# power.net
KiCad netlist of a schematic drawn in Altium Designer
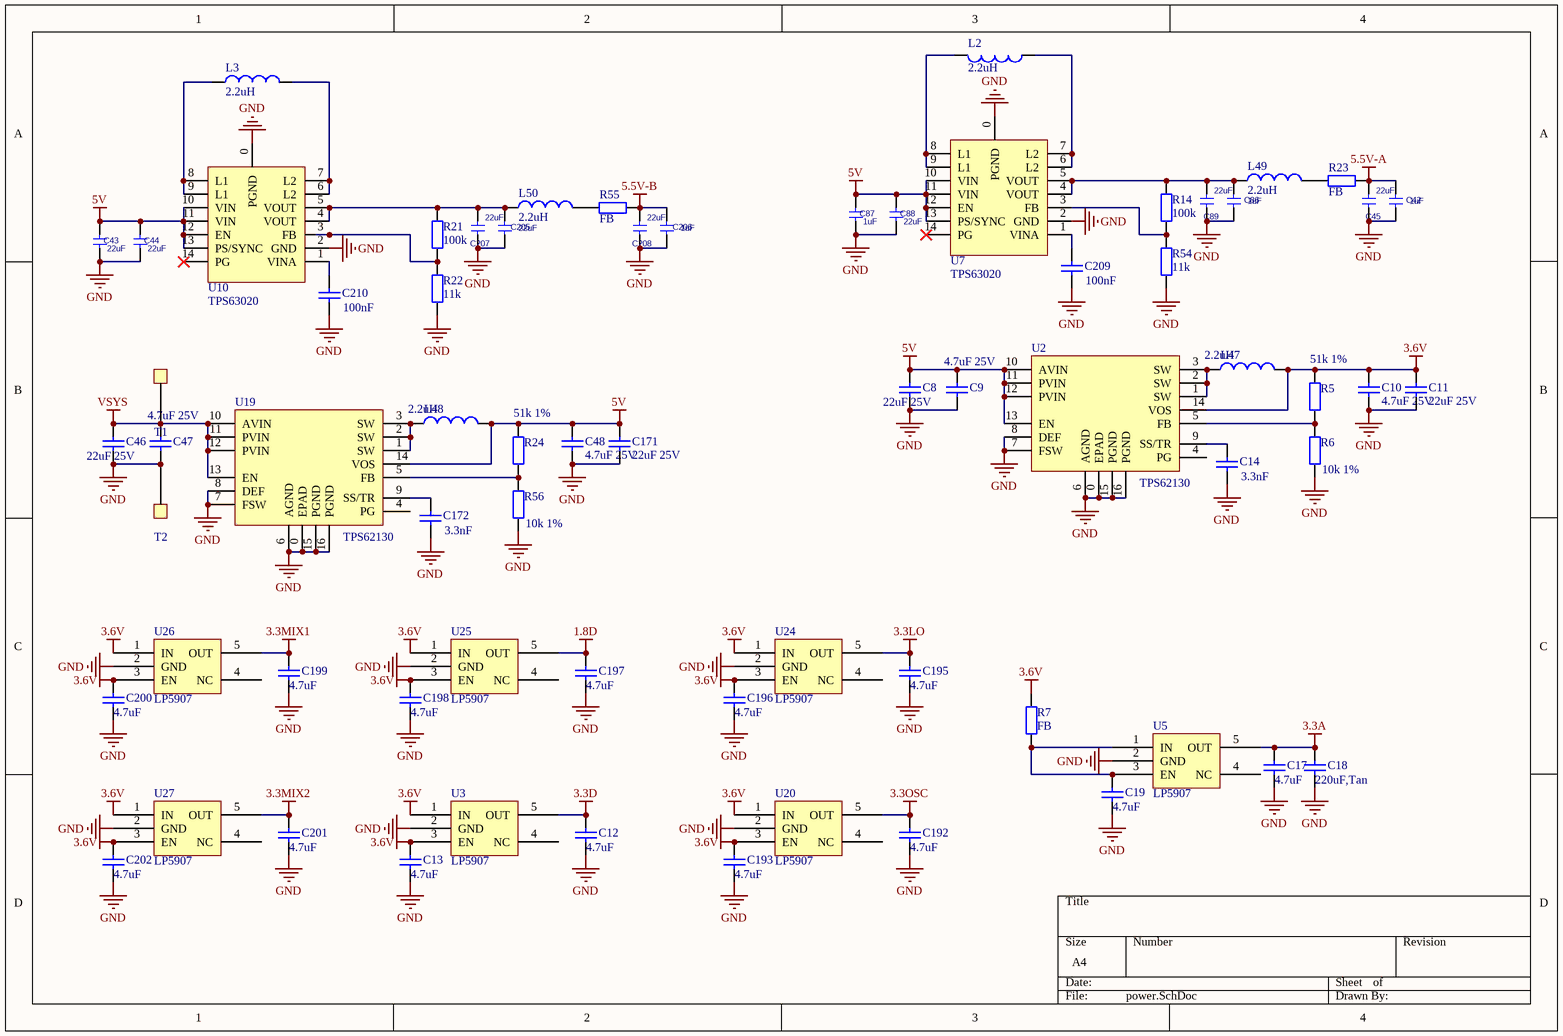
[diagram p0: power.SchDoc]

(export (version "E")
  (design (tool "Eeschema 10.0.6"))
  (components
    (comp (ref "C8")
      (value "22uF 25V")
      (footprint "0805")
      (description "Capacitor")
      (fields (field (name "Comment") "Cap") (field (name "PUBLISHER") "Altium Limited"))
      (libsource (lib "RTC6705") (part "Cap"))
    )
    (comp (ref "C9")
      (value "4.7uF 25V")
      (footprint "0603")
      (description "Capacitor")
      (fields (field (name "Comment") "Cap") (field (name "PUBLISHER") "Altium Limited"))
      (libsource (lib "RTC6705") (part "Cap"))
    )
    (comp (ref "C10")
      (value "4.7uF 25V")
      (footprint "0603")
      (description "Capacitor")
      (fields (field (name "Comment") "Cap") (field (name "PUBLISHER") "Altium Limited"))
      (libsource (lib "RTC6705") (part "Cap"))
    )
    (comp (ref "C11")
      (value "22uF 25V")
      (footprint "0805")
      (description "Capacitor")
      (fields (field (name "Comment") "Cap") (field (name "PUBLISHER") "Altium Limited"))
      (libsource (lib "RTC6705") (part "Cap"))
    )
    (comp (ref "C12")
      (value "4.7uF")
      (footprint "0603L")
      (description "Capacitor")
      (fields (field (name "PUBLISHER") "Altium Limited"))
      (libsource (lib "RTC6705") (part "Cap"))
    )
    (comp (ref "C13")
      (value "4.7uF")
      (footprint "0603L")
      (description "Capacitor")
      (fields (field (name "PUBLISHER") "Altium Limited"))
      (libsource (lib "RTC6705") (part "Cap"))
    )
    (comp (ref "C14")
      (value "3.3nF")
      (footprint "0402")
      (description "Capacitor")
      (fields (field (name "PUBLISHER") "Altium Limited"))
      (libsource (lib "RTC6705") (part "Cap"))
    )
    (comp (ref "C17")
      (value "4.7uF")
      (footprint "0603L")
      (description "Capacitor")
      (fields (field (name "PUBLISHER") "Altium Limited"))
      (libsource (lib "RTC6705") (part "Cap"))
    )
    (comp (ref "C18")
      (value "220uF,Tan")
      (footprint "1210")
      (description "Capacitor")
      (fields (field (name "PUBLISHER") "Altium Limited"))
      (libsource (lib "RTC6705") (part "Cap"))
    )
    (comp (ref "C19")
      (value "4.7uF")
      (footprint "0603L")
      (description "Capacitor")
      (fields (field (name "PUBLISHER") "Altium Limited"))
      (libsource (lib "RTC6705") (part "Cap"))
    )
    (comp (ref "C42") (value "1uF") (footprint "0805") (libsource (lib "*") (part "C")))
    (comp (ref "C43") (value "22uF") (footprint "0805") (libsource (lib "*") (part "C")))
    (comp (ref "C44") (value "22uF") (footprint "0805") (libsource (lib "*") (part "C")))
    (comp (ref "C45") (value "22uF") (footprint "0805") (libsource (lib "*") (part "C")))
    (comp (ref "C46")
      (value "22uF 25V")
      (footprint "0805")
      (description "Capacitor")
      (fields (field (name "Comment") "Cap") (field (name "PUBLISHER") "Altium Limited"))
      (libsource (lib "RTC6705") (part "Cap"))
    )
    (comp (ref "C47")
      (value "4.7uF 25V")
      (footprint "0603")
      (description "Capacitor")
      (fields (field (name "Comment") "Cap") (field (name "PUBLISHER") "Altium Limited"))
      (libsource (lib "RTC6705") (part "Cap"))
    )
    (comp (ref "C48")
      (value "4.7uF 25V")
      (footprint "0603")
      (description "Capacitor")
      (fields (field (name "Comment") "Cap") (field (name "PUBLISHER") "Altium Limited"))
      (libsource (lib "RTC6705") (part "Cap"))
    )
    (comp (ref "C86") (value "1uF") (footprint "0805") (libsource (lib "*") (part "C")))
    (comp (ref "C87") (value "1uF") (footprint "0805") (libsource (lib "*") (part "C")))
    (comp (ref "C88") (value "22uF") (footprint "0805") (libsource (lib "*") (part "C")))
    (comp (ref "C89") (value "22uF") (footprint "0805") (libsource (lib "*") (part "C")))
    (comp (ref "C171")
      (value "22uF 25V")
      (footprint "0805")
      (description "Capacitor")
      (fields (field (name "Comment") "Cap") (field (name "PUBLISHER") "Altium Limited"))
      (libsource (lib "RTC6705") (part "Cap"))
    )
    (comp (ref "C172")
      (value "3.3nF")
      (footprint "0402")
      (description "Capacitor")
      (fields (field (name "PUBLISHER") "Altium Limited"))
      (libsource (lib "RTC6705") (part "Cap"))
    )
    (comp (ref "C192")
      (value "4.7uF")
      (footprint "0603L")
      (description "Capacitor")
      (fields (field (name "PUBLISHER") "Altium Limited"))
      (libsource (lib "RTC6705") (part "Cap"))
    )
    (comp (ref "C193")
      (value "4.7uF")
      (footprint "0603L")
      (description "Capacitor")
      (fields (field (name "PUBLISHER") "Altium Limited"))
      (libsource (lib "RTC6705") (part "Cap"))
    )
    (comp (ref "C195")
      (value "4.7uF")
      (footprint "0603L")
      (description "Capacitor")
      (fields (field (name "PUBLISHER") "Altium Limited"))
      (libsource (lib "RTC6705") (part "Cap"))
    )
    (comp (ref "C196")
      (value "4.7uF")
      (footprint "0603L")
      (description "Capacitor")
      (fields (field (name "PUBLISHER") "Altium Limited"))
      (libsource (lib "RTC6705") (part "Cap"))
    )
    (comp (ref "C197")
      (value "4.7uF")
      (footprint "0603L")
      (description "Capacitor")
      (fields (field (name "PUBLISHER") "Altium Limited"))
      (libsource (lib "RTC6705") (part "Cap"))
    )
    (comp (ref "C198")
      (value "4.7uF")
      (footprint "0603L")
      (description "Capacitor")
      (fields (field (name "PUBLISHER") "Altium Limited"))
      (libsource (lib "RTC6705") (part "Cap"))
    )
    (comp (ref "C199")
      (value "4.7uF")
      (footprint "0603L")
      (description "Capacitor")
      (fields (field (name "PUBLISHER") "Altium Limited"))
      (libsource (lib "RTC6705") (part "Cap"))
    )
    (comp (ref "C200")
      (value "4.7uF")
      (footprint "0603L")
      (description "Capacitor")
      (fields (field (name "PUBLISHER") "Altium Limited"))
      (libsource (lib "RTC6705") (part "Cap"))
    )
    (comp (ref "C201")
      (value "4.7uF")
      (footprint "0603L")
      (description "Capacitor")
      (fields (field (name "PUBLISHER") "Altium Limited"))
      (libsource (lib "RTC6705") (part "Cap"))
    )
    (comp (ref "C202")
      (value "4.7uF")
      (footprint "0603L")
      (description "Capacitor")
      (fields (field (name "PUBLISHER") "Altium Limited"))
      (libsource (lib "RTC6705") (part "Cap"))
    )
    (comp (ref "C205") (value "22uF") (footprint "0805") (libsource (lib "*") (part "C")))
    (comp (ref "C206") (value "1uF") (footprint "0805") (libsource (lib "*") (part "C")))
    (comp (ref "C207") (value "22uF") (footprint "0805") (libsource (lib "*") (part "C")))
    (comp (ref "C208") (value "22uF") (footprint "0805") (libsource (lib "*") (part "C")))
    (comp (ref "C209")
      (value "100nF")
      (footprint "0402")
      (description "Capacitor")
      (fields (field (name "PUBLISHER") "Altium Limited"))
      (libsource (lib "RTC6705") (part "Cap"))
    )
    (comp (ref "C210")
      (value "100nF")
      (footprint "0402")
      (description "Capacitor")
      (fields (field (name "PUBLISHER") "Altium Limited"))
      (libsource (lib "RTC6705") (part "Cap"))
    )
    (comp (ref "L2")
      (value "2.2uH")
      (footprint "L4015")
      (description "Inductor")
      (fields (field (name "PUBLISHER") "Altium Limited"))
      (libsource (lib "Miscellaneous Devices") (part "Inductor"))
    )
    (comp (ref "L3")
      (value "2.2uH")
      (footprint "L4015")
      (description "Inductor")
      (fields (field (name "PUBLISHER") "Altium Limited"))
      (libsource (lib "Miscellaneous Devices") (part "Inductor"))
    )
    (comp (ref "L47")
      (value "2.2uH")
      (footprint "L4015")
      (description "Inductor")
      (fields (field (name "PUBLISHER") "Altium Limited"))
      (libsource (lib "Miscellaneous Devices") (part "Inductor"))
    )
    (comp (ref "L48")
      (value "2.2uH")
      (footprint "L4015")
      (description "Inductor")
      (fields (field (name "PUBLISHER") "Altium Limited"))
      (libsource (lib "Miscellaneous Devices") (part "Inductor"))
    )
    (comp (ref "L49")
      (value "2.2uH")
      (footprint "L4015")
      (description "Inductor")
      (fields (field (name "PUBLISHER") "Altium Limited"))
      (libsource (lib "Miscellaneous Devices") (part "Inductor"))
    )
    (comp (ref "L50")
      (value "2.2uH")
      (footprint "L4015")
      (description "Inductor")
      (fields (field (name "PUBLISHER") "Altium Limited"))
      (libsource (lib "Miscellaneous Devices") (part "Inductor"))
    )
    (comp (ref "R5")
      (value "51k 1%")
      (footprint "0402")
      (description "Resistor")
      (fields (field (name "PUBLISHER") "Altium Limited"))
      (libsource (lib "RTC6705") (part "Res2"))
    )
    (comp (ref "R6")
      (value "10k 1%")
      (footprint "0402")
      (description "Resistor")
      (fields (field (name "PUBLISHER") "Altium Limited"))
      (libsource (lib "RTC6705") (part "Res2"))
    )
    (comp (ref "R7")
      (value "FB")
      (footprint "0603L")
      (description "Resistor")
      (fields (field (name "PUBLISHER") "Altium Limited"))
      (libsource (lib "") (part "Res2_1"))
    )
    (comp (ref "R14")
      (value "100k")
      (footprint "0402")
      (description "Resistor")
      (fields (field (name "PUBLISHER") "Altium Limited"))
      (libsource (lib "RTC6705") (part "Res2"))
    )
    (comp (ref "R21")
      (value "100k")
      (footprint "0402")
      (description "Resistor")
      (fields (field (name "PUBLISHER") "Altium Limited"))
      (libsource (lib "RTC6705") (part "Res2"))
    )
    (comp (ref "R22")
      (value "11k")
      (footprint "0402")
      (description "Resistor")
      (fields (field (name "PUBLISHER") "Altium Limited"))
      (libsource (lib "RTC6705") (part "Res2"))
    )
    (comp (ref "R23")
      (value "FB")
      (footprint "0603L")
      (description "Resistor")
      (fields (field (name "PUBLISHER") "Altium Limited"))
      (libsource (lib "Miscellaneous Devices") (part "Res2"))
    )
    (comp (ref "R24")
      (value "51k 1%")
      (footprint "0402")
      (description "Resistor")
      (fields (field (name "PUBLISHER") "Altium Limited"))
      (libsource (lib "RTC6705") (part "Res2"))
    )
    (comp (ref "R54")
      (value "11k")
      (footprint "0402")
      (description "Resistor")
      (fields (field (name "PUBLISHER") "Altium Limited"))
      (libsource (lib "RTC6705") (part "Res2"))
    )
    (comp (ref "R55")
      (value "FB")
      (footprint "0603L")
      (description "Resistor")
      (fields (field (name "PUBLISHER") "Altium Limited"))
      (libsource (lib "Miscellaneous Devices") (part "Res2"))
    )
    (comp (ref "R56")
      (value "10k 1%")
      (footprint "0402")
      (description "Resistor")
      (fields (field (name "PUBLISHER") "Altium Limited"))
      (libsource (lib "RTC6705") (part "Res2"))
    )
    (comp (ref "T1") (value "TestPad") (footprint "TestPad") (libsource (lib "") (part "TestPad_1")))
    (comp (ref "T2") (value "TestPad") (footprint "TestPad") (libsource (lib "sch") (part "TestPad")))
    (comp (ref "U2") (value "TPS62130") (footprint "TPS62130") (libsource (lib "sch") (part "TPS62130")))
    (comp (ref "U3") (value "LP5907") (footprint "SOT23-5") (libsource (lib "RTC6705") (part "LP5907")))
    (comp (ref "U5") (value "LP5907") (footprint "SOT23-5") (libsource (lib "RTC6705") (part "LP5907")))
    (comp (ref "U7") (value "TPS63020") (footprint "TPS63020") (libsource (lib "sch") (part "TPS63020")))
    (comp (ref "U10") (value "TPS63020") (footprint "TPS63020") (libsource (lib "sch") (part "TPS63020")))
    (comp (ref "U19") (value "TPS62130") (footprint "TPS62130") (libsource (lib "sch") (part "TPS62130")))
    (comp (ref "U20") (value "LP5907") (footprint "SOT23-5") (libsource (lib "RTC6705") (part "LP5907")))
    (comp (ref "U24") (value "LP5907") (footprint "SOT23-5") (libsource (lib "RTC6705") (part "LP5907")))
    (comp (ref "U25") (value "LP5907") (footprint "SOT23-5") (libsource (lib "RTC6705") (part "LP5907")))
    (comp (ref "U26") (value "LP5907") (footprint "SOT23-5") (libsource (lib "RTC6705") (part "LP5907")))
    (comp (ref "U27") (value "LP5907") (footprint "SOT23-5") (libsource (lib "RTC6705") (part "LP5907")))
  )
  (nets
    (net (code "1") (name "1.8D") (class "Default")
      (node (ref "C197") (pin "2") (pinfunction "2_2") (pintype "passive"))
      (node (ref "U25") (pin "5") (pinfunction "OUT_5") (pintype "passive"))
    )
    (net (code "2") (name "3.3A") (class "Default")
      (node (ref "C17") (pin "2") (pinfunction "2_2") (pintype "passive"))
      (node (ref "C18") (pin "2") (pinfunction "2_2") (pintype "passive"))
      (node (ref "U5") (pin "5") (pinfunction "OUT_5") (pintype "passive"))
    )
    (net (code "3") (name "3.3D") (class "Default")
      (node (ref "C12") (pin "2") (pinfunction "2_2") (pintype "passive"))
      (node (ref "U3") (pin "5") (pinfunction "OUT_5") (pintype "passive"))
    )
    (net (code "4") (name "3.3LO") (class "Default")
      (node (ref "C195") (pin "2") (pinfunction "2_2") (pintype "passive"))
      (node (ref "U24") (pin "5") (pinfunction "OUT_5") (pintype "passive"))
    )
    (net (code "5") (name "3.3MIX1") (class "Default")
      (node (ref "C199") (pin "2") (pinfunction "2_2") (pintype "passive"))
      (node (ref "U26") (pin "5") (pinfunction "OUT_5") (pintype "passive"))
    )
    (net (code "6") (name "3.3MIX2") (class "Default")
      (node (ref "C201") (pin "2") (pinfunction "2_2") (pintype "passive"))
      (node (ref "U27") (pin "5") (pinfunction "OUT_5") (pintype "passive"))
    )
    (net (code "7") (name "3.3OSC") (class "Default")
      (node (ref "C192") (pin "2") (pinfunction "2_2") (pintype "passive"))
      (node (ref "U20") (pin "5") (pinfunction "OUT_5") (pintype "passive"))
    )
    (net (code "8") (name "3.6V") (class "Default")
      (node (ref "C10") (pin "2") (pinfunction "2_2") (pintype "passive"))
      (node (ref "C11") (pin "2") (pinfunction "2_2") (pintype "passive"))
      (node (ref "C13") (pin "2") (pinfunction "2_2") (pintype "passive"))
      (node (ref "C193") (pin "2") (pinfunction "2_2") (pintype "passive"))
      (node (ref "C196") (pin "2") (pinfunction "2_2") (pintype "passive"))
      (node (ref "C198") (pin "2") (pinfunction "2_2") (pintype "passive"))
      (node (ref "C200") (pin "2") (pinfunction "2_2") (pintype "passive"))
      (node (ref "C202") (pin "2") (pinfunction "2_2") (pintype "passive"))
      (node (ref "L47") (pin "2") (pinfunction "2_2") (pintype "passive"))
      (node (ref "R5") (pin "1") (pinfunction "1_1") (pintype "passive"))
      (node (ref "R7") (pin "2") (pinfunction "2_2") (pintype "passive"))
      (node (ref "U2") (pin "14") (pinfunction "VOS_14") (pintype "passive"))
      (node (ref "U20") (pin "1") (pinfunction "IN_1") (pintype "passive"))
      (node (ref "U20") (pin "3") (pinfunction "EN_3") (pintype "passive"))
      (node (ref "U24") (pin "1") (pinfunction "IN_1") (pintype "passive"))
      (node (ref "U24") (pin "3") (pinfunction "EN_3") (pintype "passive"))
      (node (ref "U25") (pin "1") (pinfunction "IN_1") (pintype "passive"))
      (node (ref "U25") (pin "3") (pinfunction "EN_3") (pintype "passive"))
      (node (ref "U26") (pin "1") (pinfunction "IN_1") (pintype "passive"))
      (node (ref "U26") (pin "3") (pinfunction "EN_3") (pintype "passive"))
      (node (ref "U27") (pin "1") (pinfunction "IN_1") (pintype "passive"))
      (node (ref "U27") (pin "3") (pinfunction "EN_3") (pintype "passive"))
      (node (ref "U3") (pin "1") (pinfunction "IN_1") (pintype "passive"))
      (node (ref "U3") (pin "3") (pinfunction "EN_3") (pintype "passive"))
    )
    (net (code "9") (name "5.5V-A") (class "Default")
      (node (ref "C42") (pin "1") (pinfunction "1_1") (pintype "passive"))
      (node (ref "C45") (pin "1") (pinfunction "1_1") (pintype "passive"))
      (node (ref "R23") (pin "1") (pinfunction "1_1") (pintype "passive"))
    )
    (net (code "10") (name "5.5V-B") (class "Default")
      (node (ref "C206") (pin "1") (pinfunction "1_1") (pintype "passive"))
      (node (ref "C208") (pin "1") (pinfunction "1_1") (pintype "passive"))
      (node (ref "R55") (pin "1") (pinfunction "1_1") (pintype "passive"))
    )
    (net (code "11") (name "5V") (class "Default")
      (node (ref "C171") (pin "2") (pinfunction "2_2") (pintype "passive"))
      (node (ref "C43") (pin "1") (pinfunction "1_1") (pintype "passive"))
      (node (ref "C44") (pin "1") (pinfunction "1_1") (pintype "passive"))
      (node (ref "C48") (pin "2") (pinfunction "2_2") (pintype "passive"))
      (node (ref "C8") (pin "1") (pinfunction "1_1") (pintype "passive"))
      (node (ref "C87") (pin "1") (pinfunction "1_1") (pintype "passive"))
      (node (ref "C88") (pin "1") (pinfunction "1_1") (pintype "passive"))
      (node (ref "C9") (pin "1") (pinfunction "1_1") (pintype "passive"))
      (node (ref "L48") (pin "2") (pinfunction "2_2") (pintype "passive"))
      (node (ref "R24") (pin "1") (pinfunction "1_1") (pintype "passive"))
      (node (ref "U10") (pin "10") (pinfunction "VIN_10") (pintype "passive"))
      (node (ref "U10") (pin "11") (pinfunction "VIN_11") (pintype "passive"))
      (node (ref "U10") (pin "12") (pinfunction "EN_12") (pintype "passive"))
      (node (ref "U10") (pin "13") (pinfunction "PS/SYNC_13") (pintype "passive"))
      (node (ref "U19") (pin "14") (pinfunction "VOS_14") (pintype "passive"))
      (node (ref "U2") (pin "10") (pinfunction "AVIN_10") (pintype "passive"))
      (node (ref "U2") (pin "11") (pinfunction "PVIN_11") (pintype "passive"))
      (node (ref "U2") (pin "12") (pinfunction "PVIN_12") (pintype "passive"))
      (node (ref "U2") (pin "13") (pinfunction "EN_13") (pintype "passive"))
      (node (ref "U7") (pin "10") (pinfunction "VIN_10") (pintype "passive"))
      (node (ref "U7") (pin "11") (pinfunction "VIN_11") (pintype "passive"))
      (node (ref "U7") (pin "12") (pinfunction "EN_12") (pintype "passive"))
      (node (ref "U7") (pin "13") (pinfunction "PS/SYNC_13") (pintype "passive"))
    )
    (net (code "12") (name "GND") (class "Default")
      (node (ref "C10") (pin "1") (pinfunction "1_1") (pintype "passive"))
      (node (ref "C11") (pin "1") (pinfunction "1_1") (pintype "passive"))
      (node (ref "C12") (pin "1") (pinfunction "1_1") (pintype "passive"))
      (node (ref "C13") (pin "1") (pinfunction "1_1") (pintype "passive"))
      (node (ref "C14") (pin "2") (pinfunction "2_2") (pintype "passive"))
      (node (ref "C17") (pin "1") (pinfunction "1_1") (pintype "passive"))
      (node (ref "C171") (pin "1") (pinfunction "1_1") (pintype "passive"))
      (node (ref "C172") (pin "2") (pinfunction "2_2") (pintype "passive"))
      (node (ref "C18") (pin "1") (pinfunction "1_1") (pintype "passive"))
      (node (ref "C19") (pin "1") (pinfunction "1_1") (pintype "passive"))
      (node (ref "C192") (pin "1") (pinfunction "1_1") (pintype "passive"))
      (node (ref "C193") (pin "1") (pinfunction "1_1") (pintype "passive"))
      (node (ref "C195") (pin "1") (pinfunction "1_1") (pintype "passive"))
      (node (ref "C196") (pin "1") (pinfunction "1_1") (pintype "passive"))
      (node (ref "C197") (pin "1") (pinfunction "1_1") (pintype "passive"))
      (node (ref "C198") (pin "1") (pinfunction "1_1") (pintype "passive"))
      (node (ref "C199") (pin "1") (pinfunction "1_1") (pintype "passive"))
      (node (ref "C200") (pin "1") (pinfunction "1_1") (pintype "passive"))
      (node (ref "C201") (pin "1") (pinfunction "1_1") (pintype "passive"))
      (node (ref "C202") (pin "1") (pinfunction "1_1") (pintype "passive"))
      (node (ref "C205") (pin "2") (pinfunction "2_2") (pintype "passive"))
      (node (ref "C206") (pin "2") (pinfunction "2_2") (pintype "passive"))
      (node (ref "C207") (pin "2") (pinfunction "2_2") (pintype "passive"))
      (node (ref "C208") (pin "2") (pinfunction "2_2") (pintype "passive"))
      (node (ref "C209") (pin "2") (pinfunction "2_2") (pintype "passive"))
      (node (ref "C210") (pin "2") (pinfunction "2_2") (pintype "passive"))
      (node (ref "C42") (pin "2") (pinfunction "2_2") (pintype "passive"))
      (node (ref "C43") (pin "2") (pinfunction "2_2") (pintype "passive"))
      (node (ref "C44") (pin "2") (pinfunction "2_2") (pintype "passive"))
      (node (ref "C45") (pin "2") (pinfunction "2_2") (pintype "passive"))
      (node (ref "C46") (pin "2") (pinfunction "2_2") (pintype "passive"))
      (node (ref "C47") (pin "2") (pinfunction "2_2") (pintype "passive"))
      (node (ref "C48") (pin "1") (pinfunction "1_1") (pintype "passive"))
      (node (ref "C8") (pin "2") (pinfunction "2_2") (pintype "passive"))
      (node (ref "C86") (pin "2") (pinfunction "2_2") (pintype "passive"))
      (node (ref "C87") (pin "2") (pinfunction "2_2") (pintype "passive"))
      (node (ref "C88") (pin "2") (pinfunction "2_2") (pintype "passive"))
      (node (ref "C89") (pin "2") (pinfunction "2_2") (pintype "passive"))
      (node (ref "C9") (pin "2") (pinfunction "2_2") (pintype "passive"))
      (node (ref "R22") (pin "2") (pinfunction "2_2") (pintype "passive"))
      (node (ref "R54") (pin "2") (pinfunction "2_2") (pintype "passive"))
      (node (ref "R56") (pin "2") (pinfunction "2_2") (pintype "passive"))
      (node (ref "R6") (pin "2") (pinfunction "2_2") (pintype "passive"))
      (node (ref "T2") (pin "1") (pinfunction "3_1") (pintype "passive"))
      (node (ref "U10") (pin "0") (pinfunction "PGND_0") (pintype "passive"))
      (node (ref "U10") (pin "2") (pinfunction "GND_2") (pintype "passive"))
      (node (ref "U19") (pin "0") (pinfunction "EPAD_0") (pintype "passive"))
      (node (ref "U19") (pin "15") (pinfunction "PGND_15") (pintype "passive"))
      (node (ref "U19") (pin "16") (pinfunction "PGND_16") (pintype "passive"))
      (node (ref "U19") (pin "6") (pinfunction "AGND_6") (pintype "passive"))
      (node (ref "U19") (pin "7") (pinfunction "FSW_7") (pintype "passive"))
      (node (ref "U19") (pin "8") (pinfunction "DEF_8") (pintype "passive"))
      (node (ref "U2") (pin "0") (pinfunction "EPAD_0") (pintype "passive"))
      (node (ref "U2") (pin "15") (pinfunction "PGND_15") (pintype "passive"))
      (node (ref "U2") (pin "16") (pinfunction "PGND_16") (pintype "passive"))
      (node (ref "U2") (pin "6") (pinfunction "AGND_6") (pintype "passive"))
      (node (ref "U2") (pin "7") (pinfunction "FSW_7") (pintype "passive"))
      (node (ref "U2") (pin "8") (pinfunction "DEF_8") (pintype "passive"))
      (node (ref "U20") (pin "2") (pinfunction "GND_2") (pintype "passive"))
      (node (ref "U24") (pin "2") (pinfunction "GND_2") (pintype "passive"))
      (node (ref "U25") (pin "2") (pinfunction "GND_2") (pintype "passive"))
      (node (ref "U26") (pin "2") (pinfunction "GND_2") (pintype "passive"))
      (node (ref "U27") (pin "2") (pinfunction "GND_2") (pintype "passive"))
      (node (ref "U3") (pin "2") (pinfunction "GND_2") (pintype "passive"))
      (node (ref "U5") (pin "2") (pinfunction "GND_2") (pintype "passive"))
      (node (ref "U7") (pin "0") (pinfunction "PGND_0") (pintype "passive"))
      (node (ref "U7") (pin "2") (pinfunction "GND_2") (pintype "passive"))
    )
    (net (code "13") (name "Net-(C86-Pad1)") (class "Default")
      (node (ref "C86") (pin "1") (pinfunction "1_1") (pintype "passive"))
      (node (ref "C89") (pin "1") (pinfunction "1_1") (pintype "passive"))
      (node (ref "L49") (pin "1") (pinfunction "1_1") (pintype "passive"))
      (node (ref "R14") (pin "1") (pinfunction "1_1") (pintype "passive"))
      (node (ref "U7") (pin "4") (pinfunction "VOUT_4") (pintype "passive"))
      (node (ref "U7") (pin "5") (pinfunction "VOUT_5") (pintype "passive"))
    )
    (net (code "14") (name "Net-(C205-Pad1)") (class "Default")
      (node (ref "C205") (pin "1") (pinfunction "1_1") (pintype "passive"))
      (node (ref "C207") (pin "1") (pinfunction "1_1") (pintype "passive"))
      (node (ref "L50") (pin "1") (pinfunction "1_1") (pintype "passive"))
      (node (ref "R21") (pin "1") (pinfunction "1_1") (pintype "passive"))
      (node (ref "U10") (pin "4") (pinfunction "VOUT_4") (pintype "passive"))
      (node (ref "U10") (pin "5") (pinfunction "VOUT_5") (pintype "passive"))
    )
    (net (code "15") (name "Net-(L2-Pad1)") (class "Default")
      (node (ref "L2") (pin "1") (pinfunction "1_1") (pintype "passive"))
      (node (ref "U7") (pin "6") (pinfunction "L2_6") (pintype "passive"))
      (node (ref "U7") (pin "7") (pinfunction "L2_7") (pintype "passive"))
    )
    (net (code "16") (name "Net-(L2-Pad2)") (class "Default")
      (node (ref "L2") (pin "2") (pinfunction "2_2") (pintype "passive"))
      (node (ref "U7") (pin "8") (pinfunction "L1_8") (pintype "passive"))
      (node (ref "U7") (pin "9") (pinfunction "L1_9") (pintype "passive"))
    )
    (net (code "17") (name "Net-(L3-Pad1)") (class "Default")
      (node (ref "L3") (pin "1") (pinfunction "1_1") (pintype "passive"))
      (node (ref "U10") (pin "8") (pinfunction "L1_8") (pintype "passive"))
      (node (ref "U10") (pin "9") (pinfunction "L1_9") (pintype "passive"))
    )
    (net (code "18") (name "Net-(L3-Pad2)") (class "Default")
      (node (ref "L3") (pin "2") (pinfunction "2_2") (pintype "passive"))
      (node (ref "U10") (pin "6") (pinfunction "L2_6") (pintype "passive"))
      (node (ref "U10") (pin "7") (pinfunction "L2_7") (pintype "passive"))
    )
    (net (code "19") (name "Net-(L47-Pad1)") (class "Default")
      (node (ref "L47") (pin "1") (pinfunction "1_1") (pintype "passive"))
      (node (ref "U2") (pin "1") (pinfunction "SW_1") (pintype "passive"))
      (node (ref "U2") (pin "2") (pinfunction "SW_2") (pintype "passive"))
      (node (ref "U2") (pin "3") (pinfunction "SW_3") (pintype "passive"))
    )
    (net (code "20") (name "Net-(L48-Pad1)") (class "Default")
      (node (ref "L48") (pin "1") (pinfunction "1_1") (pintype "passive"))
      (node (ref "U19") (pin "1") (pinfunction "SW_1") (pintype "passive"))
      (node (ref "U19") (pin "2") (pinfunction "SW_2") (pintype "passive"))
      (node (ref "U19") (pin "3") (pinfunction "SW_3") (pintype "passive"))
    )
    (net (code "21") (name "Net-(L49-Pad2)") (class "Default")
      (node (ref "L49") (pin "2") (pinfunction "2_2") (pintype "passive"))
      (node (ref "R23") (pin "2") (pinfunction "2_2") (pintype "passive"))
    )
    (net (code "22") (name "Net-(L50-Pad2)") (class "Default")
      (node (ref "L50") (pin "2") (pinfunction "2_2") (pintype "passive"))
      (node (ref "R55") (pin "2") (pinfunction "2_2") (pintype "passive"))
    )
    (net (code "23") (name "Net-(U2-FB)") (class "Default")
      (node (ref "R5") (pin "2") (pinfunction "2_2") (pintype "passive"))
      (node (ref "R6") (pin "1") (pinfunction "1_1") (pintype "passive"))
      (node (ref "U2") (pin "5") (pinfunction "FB_5") (pintype "passive"))
    )
    (net (code "24") (name "Net-(U2-SS{slash}TR)") (class "Default")
      (node (ref "C14") (pin "1") (pinfunction "1_1") (pintype "passive"))
      (node (ref "U2") (pin "9") (pinfunction "SS/TR_9") (pintype "passive"))
    )
    (net (code "25") (name "Net-(U5-EN)") (class "Default")
      (node (ref "C19") (pin "2") (pinfunction "2_2") (pintype "passive"))
      (node (ref "R7") (pin "1") (pinfunction "1_1") (pintype "passive"))
      (node (ref "U5") (pin "1") (pinfunction "IN_1") (pintype "passive"))
      (node (ref "U5") (pin "3") (pinfunction "EN_3") (pintype "passive"))
    )
    (net (code "26") (name "Net-(U7-FB)") (class "Default")
      (node (ref "R14") (pin "2") (pinfunction "2_2") (pintype "passive"))
      (node (ref "R54") (pin "1") (pinfunction "1_1") (pintype "passive"))
      (node (ref "U7") (pin "3") (pinfunction "FB_3") (pintype "passive"))
    )
    (net (code "27") (name "Net-(U7-VINA)") (class "Default")
      (node (ref "C209") (pin "1") (pinfunction "1_1") (pintype "passive"))
      (node (ref "U7") (pin "1") (pinfunction "VINA_1") (pintype "passive"))
    )
    (net (code "28") (name "Net-(U10-FB)") (class "Default")
      (node (ref "R21") (pin "2") (pinfunction "2_2") (pintype "passive"))
      (node (ref "R22") (pin "1") (pinfunction "1_1") (pintype "passive"))
      (node (ref "U10") (pin "3") (pinfunction "FB_3") (pintype "passive"))
    )
    (net (code "29") (name "Net-(U10-VINA)") (class "Default")
      (node (ref "C210") (pin "1") (pinfunction "1_1") (pintype "passive"))
      (node (ref "U10") (pin "1") (pinfunction "VINA_1") (pintype "passive"))
    )
    (net (code "30") (name "Net-(U19-FB)") (class "Default")
      (node (ref "R24") (pin "2") (pinfunction "2_2") (pintype "passive"))
      (node (ref "R56") (pin "1") (pinfunction "1_1") (pintype "passive"))
      (node (ref "U19") (pin "5") (pinfunction "FB_5") (pintype "passive"))
    )
    (net (code "31") (name "Net-(U19-SS{slash}TR)") (class "Default")
      (node (ref "C172") (pin "1") (pinfunction "1_1") (pintype "passive"))
      (node (ref "U19") (pin "9") (pinfunction "SS/TR_9") (pintype "passive"))
    )
    (net (code "32") (name "VSYS") (class "Default")
      (node (ref "C46") (pin "1") (pinfunction "1_1") (pintype "passive"))
      (node (ref "C47") (pin "1") (pinfunction "1_1") (pintype "passive"))
      (node (ref "T1") (pin "1") (pinfunction "3_1") (pintype "passive"))
      (node (ref "U19") (pin "10") (pinfunction "AVIN_10") (pintype "passive"))
      (node (ref "U19") (pin "11") (pinfunction "PVIN_11") (pintype "passive"))
      (node (ref "U19") (pin "12") (pinfunction "PVIN_12") (pintype "passive"))
      (node (ref "U19") (pin "13") (pinfunction "EN_13") (pintype "passive"))
    )
    (net (code "33") (name "unconnected-(U2-PG-Pad4)") (class "Default")
      (node (ref "U2") (pin "4") (pinfunction "PG_4") (pintype "passive"))
    )
    (net (code "34") (name "unconnected-(U3-NC-Pad4)") (class "Default")
      (node (ref "U3") (pin "4") (pinfunction "NC_4") (pintype "passive"))
    )
    (net (code "35") (name "unconnected-(U5-NC-Pad4)") (class "Default")
      (node (ref "U5") (pin "4") (pinfunction "NC_4") (pintype "passive"))
    )
    (net (code "36") (name "unconnected-(U7-PG-Pad14)") (class "Default")
      (node (ref "U7") (pin "14") (pinfunction "PG_14") (pintype "passive+no_connect"))
    )
    (net (code "37") (name "unconnected-(U10-PG-Pad14)") (class "Default")
      (node (ref "U10") (pin "14") (pinfunction "PG_14") (pintype "passive+no_connect"))
    )
    (net (code "38") (name "unconnected-(U19-PG-Pad4)") (class "Default")
      (node (ref "U19") (pin "4") (pinfunction "PG_4") (pintype "passive"))
    )
    (net (code "39") (name "unconnected-(U20-NC-Pad4)") (class "Default")
      (node (ref "U20") (pin "4") (pinfunction "NC_4") (pintype "passive"))
    )
    (net (code "40") (name "unconnected-(U24-NC-Pad4)") (class "Default")
      (node (ref "U24") (pin "4") (pinfunction "NC_4") (pintype "passive"))
    )
    (net (code "41") (name "unconnected-(U25-NC-Pad4)") (class "Default")
      (node (ref "U25") (pin "4") (pinfunction "NC_4") (pintype "passive"))
    )
    (net (code "42") (name "unconnected-(U26-NC-Pad4)") (class "Default")
      (node (ref "U26") (pin "4") (pinfunction "NC_4") (pintype "passive"))
    )
    (net (code "43") (name "unconnected-(U27-NC-Pad4)") (class "Default")
      (node (ref "U27") (pin "4") (pinfunction "NC_4") (pintype "passive"))
    )
  )
)
